# LEDS.net
KiCad netlist of a schematic drawn in Altium Designer
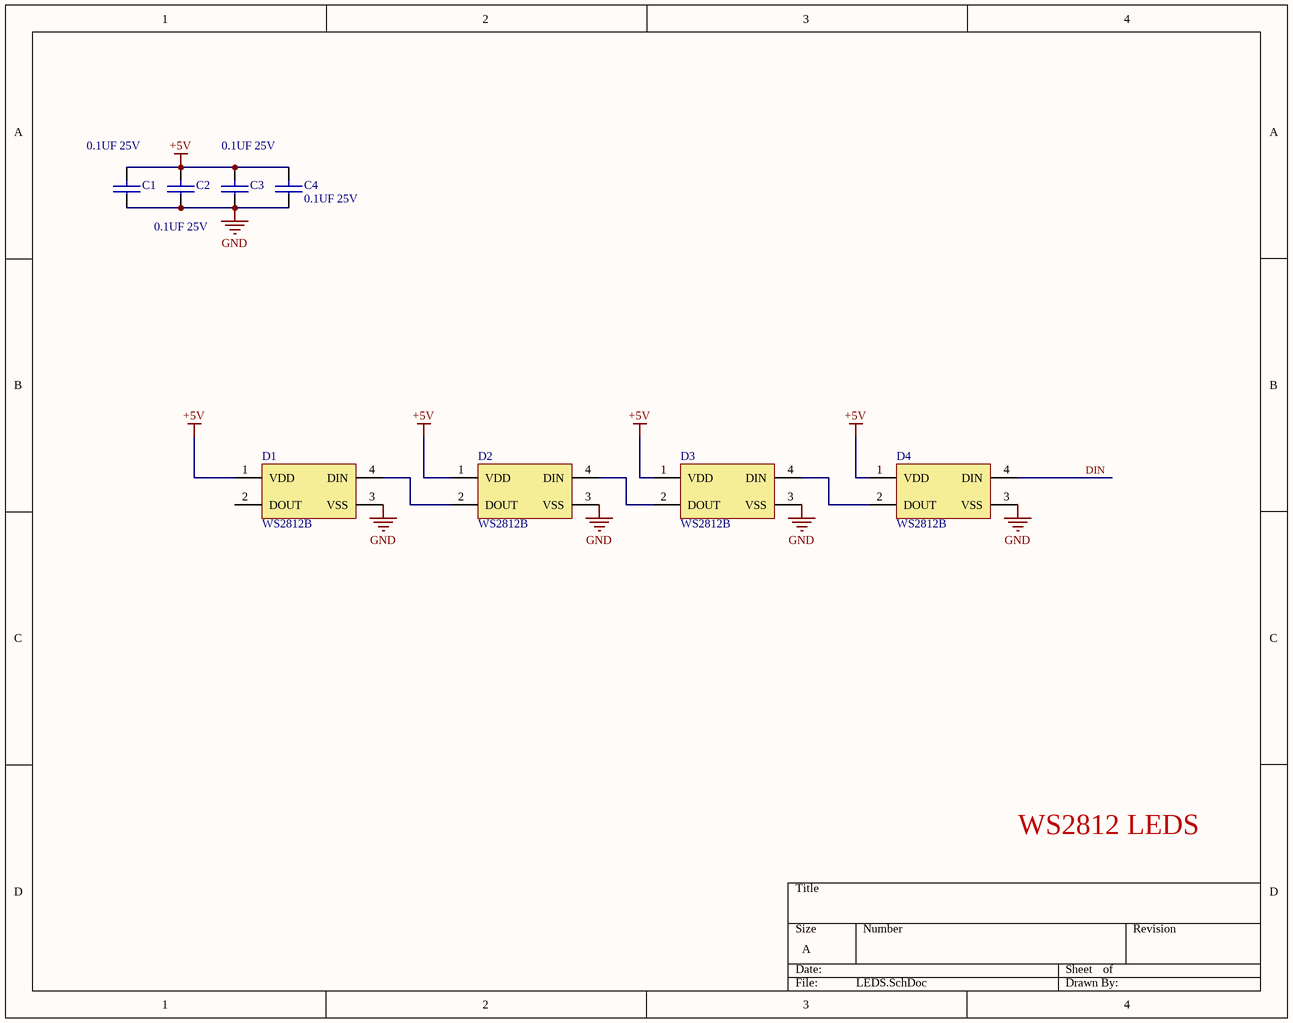
[diagram p0: LEDS.SchDoc]

(export (version "E")
  (design (tool "Eeschema 10.0.6"))
  (components
    (comp (ref "C1")
      (value "0.1UF 25V")
      (footprint "C0603")
      (description "CAP CER 0.1UF 25V X5R 0603")
      (fields
        (field (name "MANUFACTURER") "Kyocera AVX")
        (field (name "MANUFACTURER PART NUMBER") "06033D104KAT2A")
      )
      (libsource (lib "salcox") (part "06033D104KAT2A"))
    )
    (comp (ref "C2")
      (value "0.1UF 25V")
      (footprint "C0603")
      (description "CAP CER 0.1UF 25V X5R 0603")
      (fields
        (field (name "MANUFACTURER") "Kyocera AVX")
        (field (name "MANUFACTURER PART NUMBER") "06033D104KAT2A")
      )
      (libsource (lib "salcox") (part "06033D104KAT2A"))
    )
    (comp (ref "C3")
      (value "0.1UF 25V")
      (footprint "C0603")
      (description "CAP CER 0.1UF 25V X5R 0603")
      (fields
        (field (name "MANUFACTURER") "Kyocera AVX")
        (field (name "MANUFACTURER PART NUMBER") "06033D104KAT2A")
      )
      (libsource (lib "salcox") (part "06033D104KAT2A"))
    )
    (comp (ref "C4")
      (value "0.1UF 25V")
      (footprint "C0603")
      (description "CAP CER 0.1UF 25V X5R 0603")
      (fields
        (field (name "MANUFACTURER") "Kyocera AVX")
        (field (name "MANUFACTURER PART NUMBER") "06033D104KAT2A")
      )
      (libsource (lib "salcox") (part "06033D104KAT2A"))
    )
    (comp (ref "D1")
      (value "WS2812B")
      (footprint "ws2812b")
      (description "LED RGB WS2812 OR SK6812 1=10")
      (fields
        (field (name "MANUFACTURER") "Adafruit Industries LLC")
        (field (name "MANUFACTURER PART NUMBER") "1655")
      )
      (libsource (lib "salcox") (part "WS2812B"))
    )
    (comp (ref "D2")
      (value "WS2812B")
      (footprint "ws2812b")
      (description "LED RGB WS2812 OR SK6812 1=10")
      (fields
        (field (name "MANUFACTURER") "Adafruit Industries LLC")
        (field (name "MANUFACTURER PART NUMBER") "1655")
      )
      (libsource (lib "salcox") (part "WS2812B"))
    )
    (comp (ref "D3")
      (value "WS2812B")
      (footprint "ws2812b")
      (description "LED RGB WS2812 OR SK6812 1=10")
      (fields
        (field (name "MANUFACTURER") "Adafruit Industries LLC")
        (field (name "MANUFACTURER PART NUMBER") "1655")
      )
      (libsource (lib "salcox") (part "WS2812B"))
    )
    (comp (ref "D4")
      (value "WS2812B")
      (footprint "ws2812b")
      (description "LED RGB WS2812 OR SK6812 1=10")
      (fields
        (field (name "MANUFACTURER") "Adafruit Industries LLC")
        (field (name "MANUFACTURER PART NUMBER") "1655")
      )
      (libsource (lib "salcox") (part "WS2812B"))
    )
  )
  (nets
    (net (code "1") (name "+5V") (class "Default")
      (node (ref "C1") (pin "2") (pinfunction "2_2") (pintype "passive"))
      (node (ref "C2") (pin "2") (pinfunction "2_2") (pintype "passive"))
      (node (ref "C3") (pin "2") (pinfunction "2_2") (pintype "passive"))
      (node (ref "C4") (pin "2") (pinfunction "2_2") (pintype "passive"))
      (node (ref "D1") (pin "1") (pinfunction "VDD_1") (pintype "passive"))
      (node (ref "D2") (pin "1") (pinfunction "VDD_1") (pintype "passive"))
      (node (ref "D3") (pin "1") (pinfunction "VDD_1") (pintype "passive"))
      (node (ref "D4") (pin "1") (pinfunction "VDD_1") (pintype "passive"))
    )
    (net (code "2") (name "/DIN") (class "Default")
      (node (ref "D4") (pin "4") (pinfunction "DIN_4") (pintype "passive"))
    )
    (net (code "3") (name "GND") (class "Default")
      (node (ref "C1") (pin "1") (pinfunction "1_1") (pintype "passive"))
      (node (ref "C2") (pin "1") (pinfunction "1_1") (pintype "passive"))
      (node (ref "C3") (pin "1") (pinfunction "1_1") (pintype "passive"))
      (node (ref "C4") (pin "1") (pinfunction "1_1") (pintype "passive"))
      (node (ref "D1") (pin "3") (pinfunction "VSS_3") (pintype "passive"))
      (node (ref "D2") (pin "3") (pinfunction "VSS_3") (pintype "passive"))
      (node (ref "D3") (pin "3") (pinfunction "VSS_3") (pintype "passive"))
      (node (ref "D4") (pin "3") (pinfunction "VSS_3") (pintype "passive"))
    )
    (net (code "4") (name "Net-(D1-DIN)") (class "Default")
      (node (ref "D1") (pin "4") (pinfunction "DIN_4") (pintype "passive"))
      (node (ref "D2") (pin "2") (pinfunction "DOUT_2") (pintype "passive"))
    )
    (net (code "5") (name "Net-(D2-DIN)") (class "Default")
      (node (ref "D2") (pin "4") (pinfunction "DIN_4") (pintype "passive"))
      (node (ref "D3") (pin "2") (pinfunction "DOUT_2") (pintype "passive"))
    )
    (net (code "6") (name "Net-(D3-DIN)") (class "Default")
      (node (ref "D3") (pin "4") (pinfunction "DIN_4") (pintype "passive"))
      (node (ref "D4") (pin "2") (pinfunction "DOUT_2") (pintype "passive"))
    )
    (net (code "7") (name "unconnected-(D1-DOUT-Pad2)") (class "Default")
      (node (ref "D1") (pin "2") (pinfunction "DOUT_2") (pintype "passive"))
    )
  )
)
